# PoE.net
KiCad netlist of a schematic drawn in EAGLE
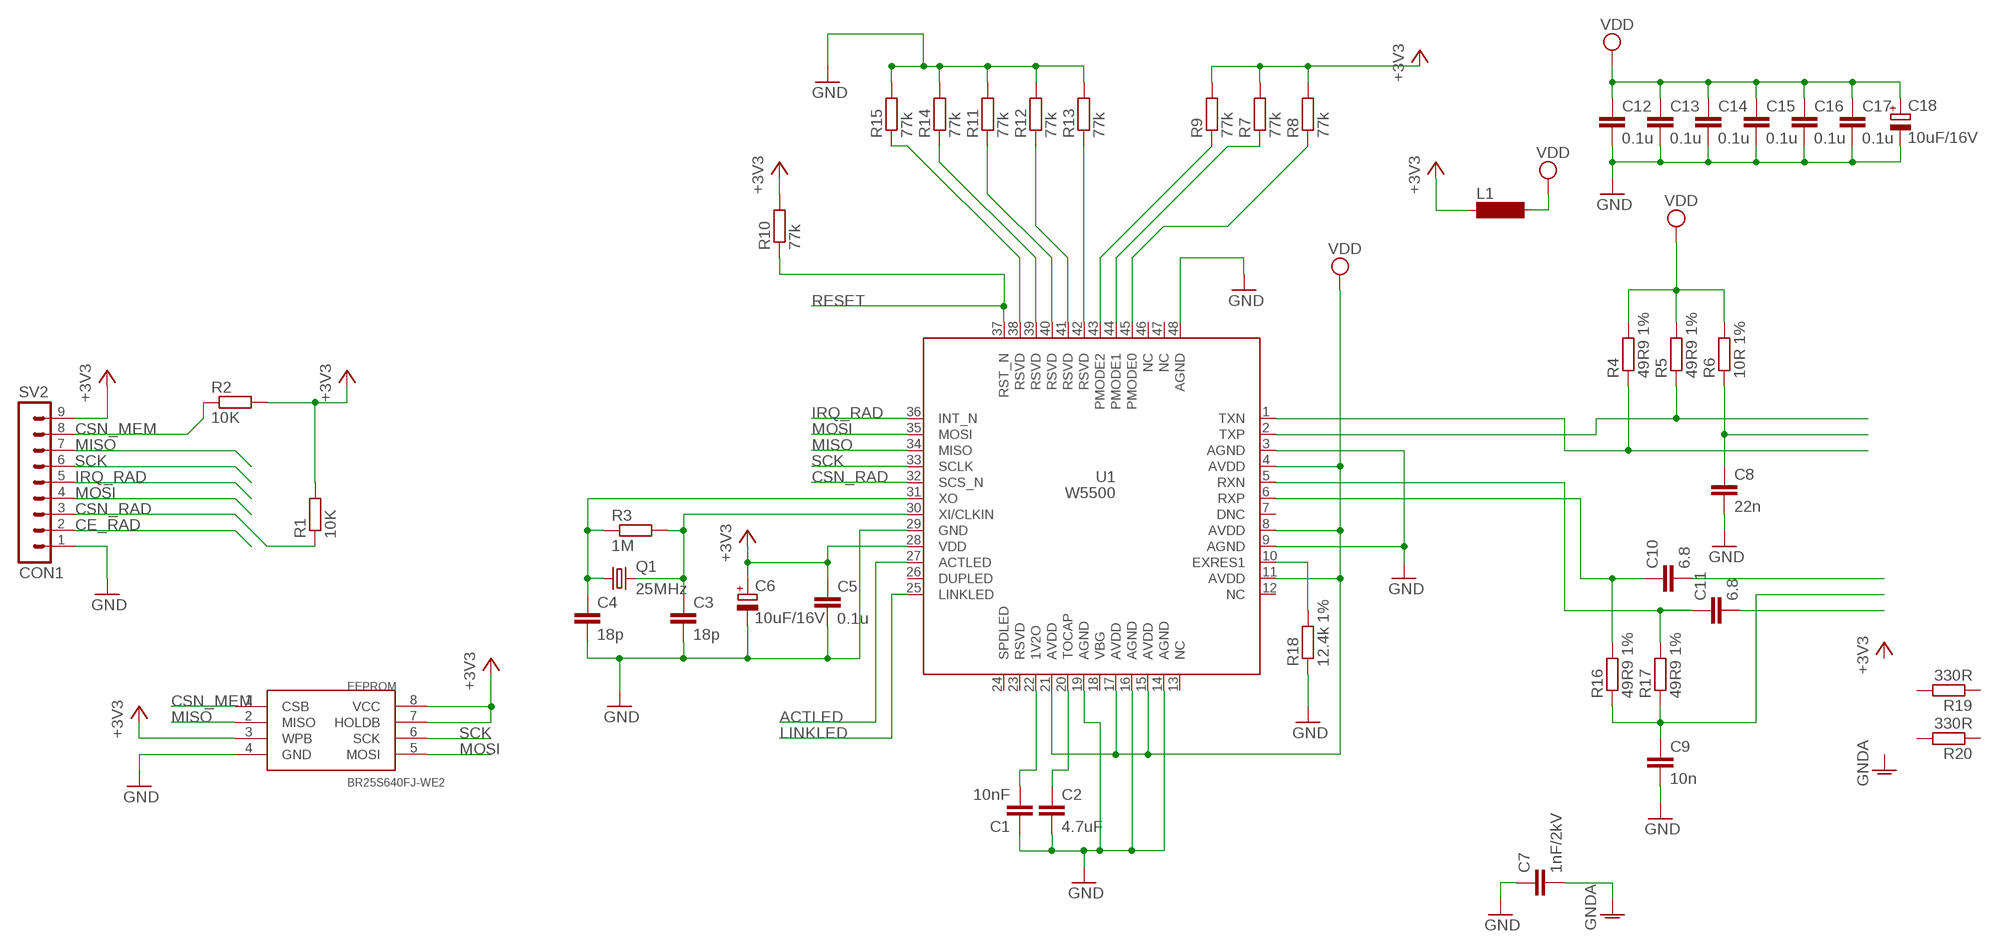
[diagram p0: schematic, sheet 1]

(export (version "E")
  (design (tool "Eeschema 10.0.6"))
  (components
    (comp (ref "C1")
      (value "10nF")
      (footprint "eagle-import:C1206")
      (libsource (lib "eagle-import") (part "C-EUC1206"))
    )
    (comp (ref "C2")
      (value "4.7uF")
      (footprint "eagle-import:C1206")
      (libsource (lib "eagle-import") (part "C-EUC1206"))
    )
    (comp (ref "C3")
      (value "18p")
      (footprint "eagle-import:C1206")
      (libsource (lib "eagle-import") (part "C-EUC1206"))
    )
    (comp (ref "C4")
      (value "18p")
      (footprint "eagle-import:C1206")
      (libsource (lib "eagle-import") (part "C-EUC1206"))
    )
    (comp (ref "C5")
      (value "0.1u")
      (footprint "eagle-import:C1206")
      (libsource (lib "eagle-import") (part "C-EUC1206"))
    )
    (comp (ref "C6")
      (value "10uF/16V")
      (footprint "eagle-import:153CLV-0505")
      (libsource (lib "eagle-import") (part "CPOL-EU153CLV-0505"))
    )
    (comp (ref "C7")
      (value "1nF/2kV")
      (footprint "eagle-import:C1206")
      (libsource (lib "eagle-import") (part "C-EUC1206"))
    )
    (comp (ref "C8")
      (value "22n")
      (footprint "eagle-import:C1206")
      (libsource (lib "eagle-import") (part "C-EUC1206"))
    )
    (comp (ref "C9")
      (value "10n")
      (footprint "eagle-import:C1206")
      (libsource (lib "eagle-import") (part "C-EUC1206"))
    )
    (comp (ref "C10")
      (value "6.8")
      (footprint "eagle-import:C1206")
      (libsource (lib "eagle-import") (part "C-EUC1206"))
    )
    (comp (ref "C11")
      (value "6.8")
      (footprint "eagle-import:C1206")
      (libsource (lib "eagle-import") (part "C-EUC1206"))
    )
    (comp (ref "C12")
      (value "0.1u")
      (footprint "eagle-import:C1206")
      (libsource (lib "eagle-import") (part "C-EUC1206"))
    )
    (comp (ref "C13")
      (value "0.1u")
      (footprint "eagle-import:C1206")
      (libsource (lib "eagle-import") (part "C-EUC1206"))
    )
    (comp (ref "C14")
      (value "0.1u")
      (footprint "eagle-import:C1206")
      (libsource (lib "eagle-import") (part "C-EUC1206"))
    )
    (comp (ref "C15")
      (value "0.1u")
      (footprint "eagle-import:C1206")
      (libsource (lib "eagle-import") (part "C-EUC1206"))
    )
    (comp (ref "C16")
      (value "0.1u")
      (footprint "eagle-import:C1206")
      (libsource (lib "eagle-import") (part "C-EUC1206"))
    )
    (comp (ref "C17")
      (value "0.1u")
      (footprint "eagle-import:C1206")
      (libsource (lib "eagle-import") (part "C-EUC1206"))
    )
    (comp (ref "C18")
      (value "10uF/16V")
      (footprint "eagle-import:153CLV-0405")
      (libsource (lib "eagle-import") (part "CPOL-EU153CLV-0405"))
    )
    (comp (ref "EEPROM")
      (value "BR25S640FJ-WE2")
      (footprint "eagle-import:SO8")
      (libsource (lib "eagle-import") (part "BR25S640FJ-WE2"))
    )
    (comp (ref "L1")
      (value "MS50")
      (footprint "eagle-import:MS50")
      (libsource (lib "eagle-import") (part "MS50"))
    )
    (comp (ref "Q1")
      (value "25MHz")
      (footprint "eagle-import:HC49UP")
      (libsource (lib "eagle-import") (part "CRYSTALHC49UP"))
    )
    (comp (ref "R1")
      (value "10K")
      (footprint "eagle-import:R1206")
      (libsource (lib "eagle-import") (part "R-EU_R1206"))
    )
    (comp (ref "R2")
      (value "10K")
      (footprint "eagle-import:R1206")
      (libsource (lib "eagle-import") (part "R-EU_R1206"))
    )
    (comp (ref "R3")
      (value "1M")
      (footprint "eagle-import:R1206")
      (libsource (lib "eagle-import") (part "R-EU_R1206"))
    )
    (comp (ref "R4")
      (value "49R9 1%")
      (footprint "eagle-import:R1206")
      (libsource (lib "eagle-import") (part "R-EU_R1206"))
    )
    (comp (ref "R5")
      (value "49R9 1%")
      (footprint "eagle-import:R1206")
      (libsource (lib "eagle-import") (part "R-EU_R1206"))
    )
    (comp (ref "R6")
      (value "10R 1%")
      (footprint "eagle-import:R1206")
      (libsource (lib "eagle-import") (part "R-EU_R1206"))
    )
    (comp (ref "R7")
      (value "77k")
      (footprint "eagle-import:R1206")
      (libsource (lib "eagle-import") (part "R-EU_R1206"))
    )
    (comp (ref "R8")
      (value "77k")
      (footprint "eagle-import:R1206")
      (libsource (lib "eagle-import") (part "R-EU_R1206"))
    )
    (comp (ref "R9")
      (value "77k")
      (footprint "eagle-import:R1206")
      (libsource (lib "eagle-import") (part "R-EU_R1206"))
    )
    (comp (ref "R10")
      (value "77k")
      (footprint "eagle-import:R1206")
      (libsource (lib "eagle-import") (part "R-EU_R1206"))
    )
    (comp (ref "R11")
      (value "77k")
      (footprint "eagle-import:R1206")
      (libsource (lib "eagle-import") (part "R-EU_R1206"))
    )
    (comp (ref "R12")
      (value "77k")
      (footprint "eagle-import:R1206")
      (libsource (lib "eagle-import") (part "R-EU_R1206"))
    )
    (comp (ref "R13")
      (value "77k")
      (footprint "eagle-import:R1206")
      (libsource (lib "eagle-import") (part "R-EU_R1206"))
    )
    (comp (ref "R14")
      (value "77k")
      (footprint "eagle-import:R1206")
      (libsource (lib "eagle-import") (part "R-EU_R1206"))
    )
    (comp (ref "R15")
      (value "77k")
      (footprint "eagle-import:R1206")
      (libsource (lib "eagle-import") (part "R-EU_R1206"))
    )
    (comp (ref "R16")
      (value "49R9 1%")
      (footprint "eagle-import:R1206")
      (libsource (lib "eagle-import") (part "R-EU_R1206"))
    )
    (comp (ref "R17")
      (value "49R9 1%")
      (footprint "eagle-import:R1206")
      (libsource (lib "eagle-import") (part "R-EU_R1206"))
    )
    (comp (ref "R18")
      (value "12.4k 1%")
      (footprint "eagle-import:R1206")
      (libsource (lib "eagle-import") (part "R-EU_R1206"))
    )
    (comp (ref "R19")
      (value "330R")
      (footprint "eagle-import:R1206")
      (libsource (lib "eagle-import") (part "R-EU_R1206"))
    )
    (comp (ref "R20")
      (value "330R")
      (footprint "eagle-import:R1206")
      (libsource (lib "eagle-import") (part "R-EU_R1206"))
    )
    (comp (ref "SV2")
      (value "CON1")
      (footprint "eagle-import:MA09-1W")
      (libsource (lib "eagle-import") (part "MA09-1W"))
    )
    (comp (ref "U1")
      (value "W5500")
      (footprint "eagle-import:W5500")
      (libsource (lib "eagle-import") (part "W5500"))
    )
  )
  (nets
    (net (code "1") (name "+3V3") (class "Default")
      (node (ref "C5") (pin "1") (pinfunction "1_1") (pintype "passive"))
      (node (ref "C6") (pin "+") (pinfunction "+_+") (pintype "passive"))
      (node (ref "EEPROM") (pin "3") (pinfunction "WPB_3") (pintype "bidirectional"))
      (node (ref "EEPROM") (pin "7") (pinfunction "HOLDB_7") (pintype "bidirectional"))
      (node (ref "EEPROM") (pin "8") (pinfunction "VCC_8") (pintype "bidirectional"))
      (node (ref "L1") (pin "1") (pinfunction "1_1") (pintype "passive"))
      (node (ref "R1") (pin "2") (pinfunction "2_2") (pintype "passive"))
      (node (ref "R10") (pin "2") (pinfunction "2_2") (pintype "passive"))
      (node (ref "R2") (pin "2") (pinfunction "2_2") (pintype "passive"))
      (node (ref "R7") (pin "2") (pinfunction "2_2") (pintype "passive"))
      (node (ref "R8") (pin "2") (pinfunction "2_2") (pintype "passive"))
      (node (ref "R9") (pin "2") (pinfunction "2_2") (pintype "passive"))
      (node (ref "SV2") (pin "9") (pinfunction "9_9") (pintype "passive"))
      (node (ref "U1") (pin "28") (pinfunction "VDD_28") (pintype "passive"))
    )
    (net (code "2") (name "/ACTLED") (class "Default")
      (node (ref "U1") (pin "27") (pinfunction "ACTLED_27") (pintype "passive"))
    )
    (net (code "3") (name "/CE_RAD") (class "Default")
      (node (ref "SV2") (pin "2") (pinfunction "2_2") (pintype "passive"))
    )
    (net (code "4") (name "/CSN_MEM") (class "Default")
      (node (ref "EEPROM") (pin "1") (pinfunction "CSB_1") (pintype "bidirectional"))
      (node (ref "R2") (pin "1") (pinfunction "1_1") (pintype "passive"))
      (node (ref "SV2") (pin "8") (pinfunction "8_8") (pintype "passive"))
    )
    (net (code "5") (name "/CSN_RAD") (class "Default")
      (node (ref "R1") (pin "1") (pinfunction "1_1") (pintype "passive"))
      (node (ref "SV2") (pin "3") (pinfunction "3_3") (pintype "passive"))
      (node (ref "U1") (pin "32") (pinfunction "SCS_N_32") (pintype "passive"))
    )
    (net (code "6") (name "/IRQ_RAD") (class "Default")
      (node (ref "SV2") (pin "5") (pinfunction "5_5") (pintype "passive"))
      (node (ref "U1") (pin "36") (pinfunction "INT_N_36") (pintype "passive"))
    )
    (net (code "7") (name "/LINKLED") (class "Default")
      (node (ref "U1") (pin "25") (pinfunction "LINKLED_25") (pintype "passive"))
    )
    (net (code "8") (name "/MISO") (class "Default")
      (node (ref "EEPROM") (pin "2") (pinfunction "MISO_2") (pintype "bidirectional"))
      (node (ref "SV2") (pin "7") (pinfunction "7_7") (pintype "passive"))
      (node (ref "U1") (pin "34") (pinfunction "MISO_34") (pintype "passive"))
    )
    (net (code "9") (name "/MOSI") (class "Default")
      (node (ref "EEPROM") (pin "5") (pinfunction "MOSI_5") (pintype "bidirectional"))
      (node (ref "SV2") (pin "4") (pinfunction "4_4") (pintype "passive"))
      (node (ref "U1") (pin "35") (pinfunction "MOSI_35") (pintype "passive"))
    )
    (net (code "10") (name "/RESET") (class "Default")
      (node (ref "R10") (pin "1") (pinfunction "1_1") (pintype "passive"))
      (node (ref "U1") (pin "37") (pinfunction "RST_N_37") (pintype "passive"))
    )
    (net (code "11") (name "/SCK") (class "Default")
      (node (ref "EEPROM") (pin "6") (pinfunction "SCK_6") (pintype "bidirectional"))
      (node (ref "SV2") (pin "6") (pinfunction "6_6") (pintype "passive"))
      (node (ref "U1") (pin "33") (pinfunction "SCLK_33") (pintype "passive"))
    )
    (net (code "12") (name "GND") (class "Default")
      (node (ref "C1") (pin "1") (pinfunction "1_1") (pintype "passive"))
      (node (ref "C12") (pin "2") (pinfunction "2_2") (pintype "passive"))
      (node (ref "C13") (pin "2") (pinfunction "2_2") (pintype "passive"))
      (node (ref "C14") (pin "2") (pinfunction "2_2") (pintype "passive"))
      (node (ref "C15") (pin "2") (pinfunction "2_2") (pintype "passive"))
      (node (ref "C16") (pin "2") (pinfunction "2_2") (pintype "passive"))
      (node (ref "C17") (pin "2") (pinfunction "2_2") (pintype "passive"))
      (node (ref "C18") (pin "-") (pinfunction "-_-") (pintype "passive"))
      (node (ref "C2") (pin "2") (pinfunction "2_2") (pintype "passive"))
      (node (ref "C3") (pin "2") (pinfunction "2_2") (pintype "passive"))
      (node (ref "C4") (pin "2") (pinfunction "2_2") (pintype "passive"))
      (node (ref "C5") (pin "2") (pinfunction "2_2") (pintype "passive"))
      (node (ref "C6") (pin "-") (pinfunction "-_-") (pintype "passive"))
      (node (ref "C7") (pin "1") (pinfunction "1_1") (pintype "passive"))
      (node (ref "C8") (pin "2") (pinfunction "2_2") (pintype "passive"))
      (node (ref "C9") (pin "2") (pinfunction "2_2") (pintype "passive"))
      (node (ref "EEPROM") (pin "4") (pinfunction "GND_4") (pintype "bidirectional"))
      (node (ref "R11") (pin "2") (pinfunction "2_2") (pintype "passive"))
      (node (ref "R12") (pin "2") (pinfunction "2_2") (pintype "passive"))
      (node (ref "R13") (pin "2") (pinfunction "2_2") (pintype "passive"))
      (node (ref "R14") (pin "2") (pinfunction "2_2") (pintype "passive"))
      (node (ref "R15") (pin "2") (pinfunction "2_2") (pintype "passive"))
      (node (ref "R18") (pin "1") (pinfunction "1_1") (pintype "passive"))
      (node (ref "SV2") (pin "1") (pinfunction "1_1") (pintype "passive"))
      (node (ref "U1") (pin "14") (pinfunction "AGND_14") (pintype "passive"))
      (node (ref "U1") (pin "16") (pinfunction "AGND_16") (pintype "passive"))
      (node (ref "U1") (pin "19") (pinfunction "AGND_19") (pintype "passive"))
      (node (ref "U1") (pin "29") (pinfunction "GND_29") (pintype "passive"))
      (node (ref "U1") (pin "3") (pinfunction "AGND_3") (pintype "passive"))
      (node (ref "U1") (pin "48") (pinfunction "AGND_48") (pintype "passive"))
      (node (ref "U1") (pin "9") (pinfunction "AGND_9") (pintype "passive"))
    )
    (net (code "13") (name "GNDA") (class "Default")
      (node (ref "C7") (pin "2") (pinfunction "2_2") (pintype "passive"))
    )
    (net (code "14") (name "Net-(C8-Pad1)") (class "Default")
      (node (ref "C8") (pin "1") (pinfunction "1_1") (pintype "passive"))
      (node (ref "R6") (pin "1") (pinfunction "1_1") (pintype "passive"))
    )
    (net (code "15") (name "Net-(C9-Pad1)") (class "Default")
      (node (ref "C9") (pin "1") (pinfunction "1_1") (pintype "passive"))
      (node (ref "R16") (pin "1") (pinfunction "1_1") (pintype "passive"))
      (node (ref "R17") (pin "1") (pinfunction "1_1") (pintype "passive"))
    )
    (net (code "16") (name "Net-(R11-Pad1)") (class "Default")
      (node (ref "R11") (pin "1") (pinfunction "1_1") (pintype "passive"))
      (node (ref "U1") (pin "40") (pinfunction "RSVD_40") (pintype "passive"))
    )
    (net (code "17") (name "Net-(R12-Pad1)") (class "Default")
      (node (ref "R12") (pin "1") (pinfunction "1_1") (pintype "passive"))
      (node (ref "U1") (pin "41") (pinfunction "RSVD_41") (pintype "passive"))
    )
    (net (code "18") (name "Net-(R13-Pad1)") (class "Default")
      (node (ref "R13") (pin "1") (pinfunction "1_1") (pintype "passive"))
      (node (ref "U1") (pin "42") (pinfunction "RSVD_42") (pintype "passive"))
    )
    (net (code "19") (name "Net-(R14-Pad1)") (class "Default")
      (node (ref "R14") (pin "1") (pinfunction "1_1") (pintype "passive"))
      (node (ref "U1") (pin "39") (pinfunction "RSVD_39") (pintype "passive"))
    )
    (net (code "20") (name "Net-(R15-Pad1)") (class "Default")
      (node (ref "R15") (pin "1") (pinfunction "1_1") (pintype "passive"))
      (node (ref "U1") (pin "38") (pinfunction "RSVD_38") (pintype "passive"))
    )
    (net (code "21") (name "Net-(U1-1V2O)") (class "Default")
      (node (ref "C1") (pin "2") (pinfunction "2_2") (pintype "passive"))
      (node (ref "U1") (pin "22") (pinfunction "1V2O_22") (pintype "passive"))
    )
    (net (code "22") (name "Net-(U1-EXRES1)") (class "Default")
      (node (ref "R18") (pin "2") (pinfunction "2_2") (pintype "passive"))
      (node (ref "U1") (pin "10") (pinfunction "EXRES1_10") (pintype "passive"))
    )
    (net (code "23") (name "Net-(U1-PMODE0)") (class "Default")
      (node (ref "R8") (pin "1") (pinfunction "1_1") (pintype "passive"))
      (node (ref "U1") (pin "45") (pinfunction "PMODE0_45") (pintype "passive"))
    )
    (net (code "24") (name "Net-(U1-PMODE1)") (class "Default")
      (node (ref "R7") (pin "1") (pinfunction "1_1") (pintype "passive"))
      (node (ref "U1") (pin "44") (pinfunction "PMODE1_44") (pintype "passive"))
    )
    (net (code "25") (name "Net-(U1-PMODE2)") (class "Default")
      (node (ref "R9") (pin "1") (pinfunction "1_1") (pintype "passive"))
      (node (ref "U1") (pin "43") (pinfunction "PMODE2_43") (pintype "passive"))
    )
    (net (code "26") (name "Net-(U1-RXN)") (class "Default")
      (node (ref "C11") (pin "1") (pinfunction "1_1") (pintype "passive"))
      (node (ref "R17") (pin "2") (pinfunction "2_2") (pintype "passive"))
      (node (ref "U1") (pin "5") (pinfunction "RXN_5") (pintype "passive"))
    )
    (net (code "27") (name "Net-(U1-RXP)") (class "Default")
      (node (ref "C10") (pin "1") (pinfunction "1_1") (pintype "passive"))
      (node (ref "R16") (pin "2") (pinfunction "2_2") (pintype "passive"))
      (node (ref "U1") (pin "6") (pinfunction "RXP_6") (pintype "passive"))
    )
    (net (code "28") (name "Net-(U1-TOCAP)") (class "Default")
      (node (ref "C2") (pin "1") (pinfunction "1_1") (pintype "passive"))
      (node (ref "U1") (pin "20") (pinfunction "TOCAP_20") (pintype "passive"))
    )
    (net (code "29") (name "Net-(U1-TXN)") (class "Default")
      (node (ref "R4") (pin "1") (pinfunction "1_1") (pintype "passive"))
      (node (ref "U1") (pin "1") (pinfunction "TXN_1") (pintype "passive"))
    )
    (net (code "30") (name "Net-(U1-TXP)") (class "Default")
      (node (ref "R5") (pin "1") (pinfunction "1_1") (pintype "passive"))
      (node (ref "U1") (pin "2") (pinfunction "TXP_2") (pintype "passive"))
    )
    (net (code "31") (name "Net-(U1-XI{slash}CLKIN)") (class "Default")
      (node (ref "C3") (pin "1") (pinfunction "1_1") (pintype "passive"))
      (node (ref "Q1") (pin "2") (pinfunction "2_2") (pintype "passive"))
      (node (ref "R3") (pin "2") (pinfunction "2_2") (pintype "passive"))
      (node (ref "U1") (pin "30") (pinfunction "XI/CLKIN_30") (pintype "passive"))
    )
    (net (code "32") (name "Net-(U1-XO)") (class "Default")
      (node (ref "C4") (pin "1") (pinfunction "1_1") (pintype "passive"))
      (node (ref "Q1") (pin "1") (pinfunction "1_1") (pintype "passive"))
      (node (ref "R3") (pin "1") (pinfunction "1_1") (pintype "passive"))
      (node (ref "U1") (pin "31") (pinfunction "XO_31") (pintype "passive"))
    )
    (net (code "33") (name "VDD") (class "Default")
      (node (ref "C12") (pin "1") (pinfunction "1_1") (pintype "passive"))
      (node (ref "C13") (pin "1") (pinfunction "1_1") (pintype "passive"))
      (node (ref "C14") (pin "1") (pinfunction "1_1") (pintype "passive"))
      (node (ref "C15") (pin "1") (pinfunction "1_1") (pintype "passive"))
      (node (ref "C16") (pin "1") (pinfunction "1_1") (pintype "passive"))
      (node (ref "C17") (pin "1") (pinfunction "1_1") (pintype "passive"))
      (node (ref "C18") (pin "+") (pinfunction "+_+") (pintype "passive"))
      (node (ref "L1") (pin "2") (pinfunction "2_2") (pintype "passive"))
      (node (ref "R4") (pin "2") (pinfunction "2_2") (pintype "passive"))
      (node (ref "R5") (pin "2") (pinfunction "2_2") (pintype "passive"))
      (node (ref "R6") (pin "2") (pinfunction "2_2") (pintype "passive"))
      (node (ref "U1") (pin "11") (pinfunction "AVDD_11") (pintype "passive"))
      (node (ref "U1") (pin "15") (pinfunction "AVDD_15") (pintype "passive"))
      (node (ref "U1") (pin "17") (pinfunction "AVDD_17") (pintype "passive"))
      (node (ref "U1") (pin "21") (pinfunction "AVDD_21") (pintype "passive"))
      (node (ref "U1") (pin "4") (pinfunction "AVDD_4") (pintype "passive"))
      (node (ref "U1") (pin "8") (pinfunction "AVDD_8") (pintype "passive"))
    )
    (net (code "34") (name "unconnected-(C10-Pad2)") (class "Default")
      (node (ref "C10") (pin "2") (pinfunction "2_2") (pintype "passive"))
    )
    (net (code "35") (name "unconnected-(C11-Pad2)") (class "Default")
      (node (ref "C11") (pin "2") (pinfunction "2_2") (pintype "passive"))
    )
    (net (code "36") (name "unconnected-(R19-Pad1)") (class "Default")
      (node (ref "R19") (pin "1") (pinfunction "1_1") (pintype "passive"))
    )
    (net (code "37") (name "unconnected-(R19-Pad2)") (class "Default")
      (node (ref "R19") (pin "2") (pinfunction "2_2") (pintype "passive"))
    )
    (net (code "38") (name "unconnected-(R20-Pad1)") (class "Default")
      (node (ref "R20") (pin "1") (pinfunction "1_1") (pintype "passive"))
    )
    (net (code "39") (name "unconnected-(R20-Pad2)") (class "Default")
      (node (ref "R20") (pin "2") (pinfunction "2_2") (pintype "passive"))
    )
    (net (code "40") (name "unconnected-(U1-DNC-Pad7)") (class "Default")
      (node (ref "U1") (pin "7") (pinfunction "DNC_7") (pintype "passive"))
    )
    (net (code "41") (name "unconnected-(U1-DUPLED-Pad26)") (class "Default")
      (node (ref "U1") (pin "26") (pinfunction "DUPLED_26") (pintype "passive"))
    )
    (net (code "42") (name "unconnected-(U1-NC-Pad12)") (class "Default")
      (node (ref "U1") (pin "12") (pinfunction "NC_12") (pintype "passive"))
    )
    (net (code "43") (name "unconnected-(U1-NC-Pad13)") (class "Default")
      (node (ref "U1") (pin "13") (pinfunction "NC_13") (pintype "passive"))
    )
    (net (code "44") (name "unconnected-(U1-NC-Pad46)") (class "Default")
      (node (ref "U1") (pin "46") (pinfunction "NC_46") (pintype "passive"))
    )
    (net (code "45") (name "unconnected-(U1-NC-Pad47)") (class "Default")
      (node (ref "U1") (pin "47") (pinfunction "NC_47") (pintype "passive"))
    )
    (net (code "46") (name "unconnected-(U1-RSVD-Pad23)") (class "Default")
      (node (ref "U1") (pin "23") (pinfunction "RSVD_23") (pintype "passive"))
    )
    (net (code "47") (name "unconnected-(U1-SPDLED-Pad24)") (class "Default")
      (node (ref "U1") (pin "24") (pinfunction "SPDLED_24") (pintype "passive"))
    )
    (net (code "48") (name "unconnected-(U1-VBG-Pad18)") (class "Default")
      (node (ref "U1") (pin "18") (pinfunction "VBG_18") (pintype "passive"))
    )
  )
)
